# Ethernet.net
KiCad netlist of a schematic drawn in Altium Designer
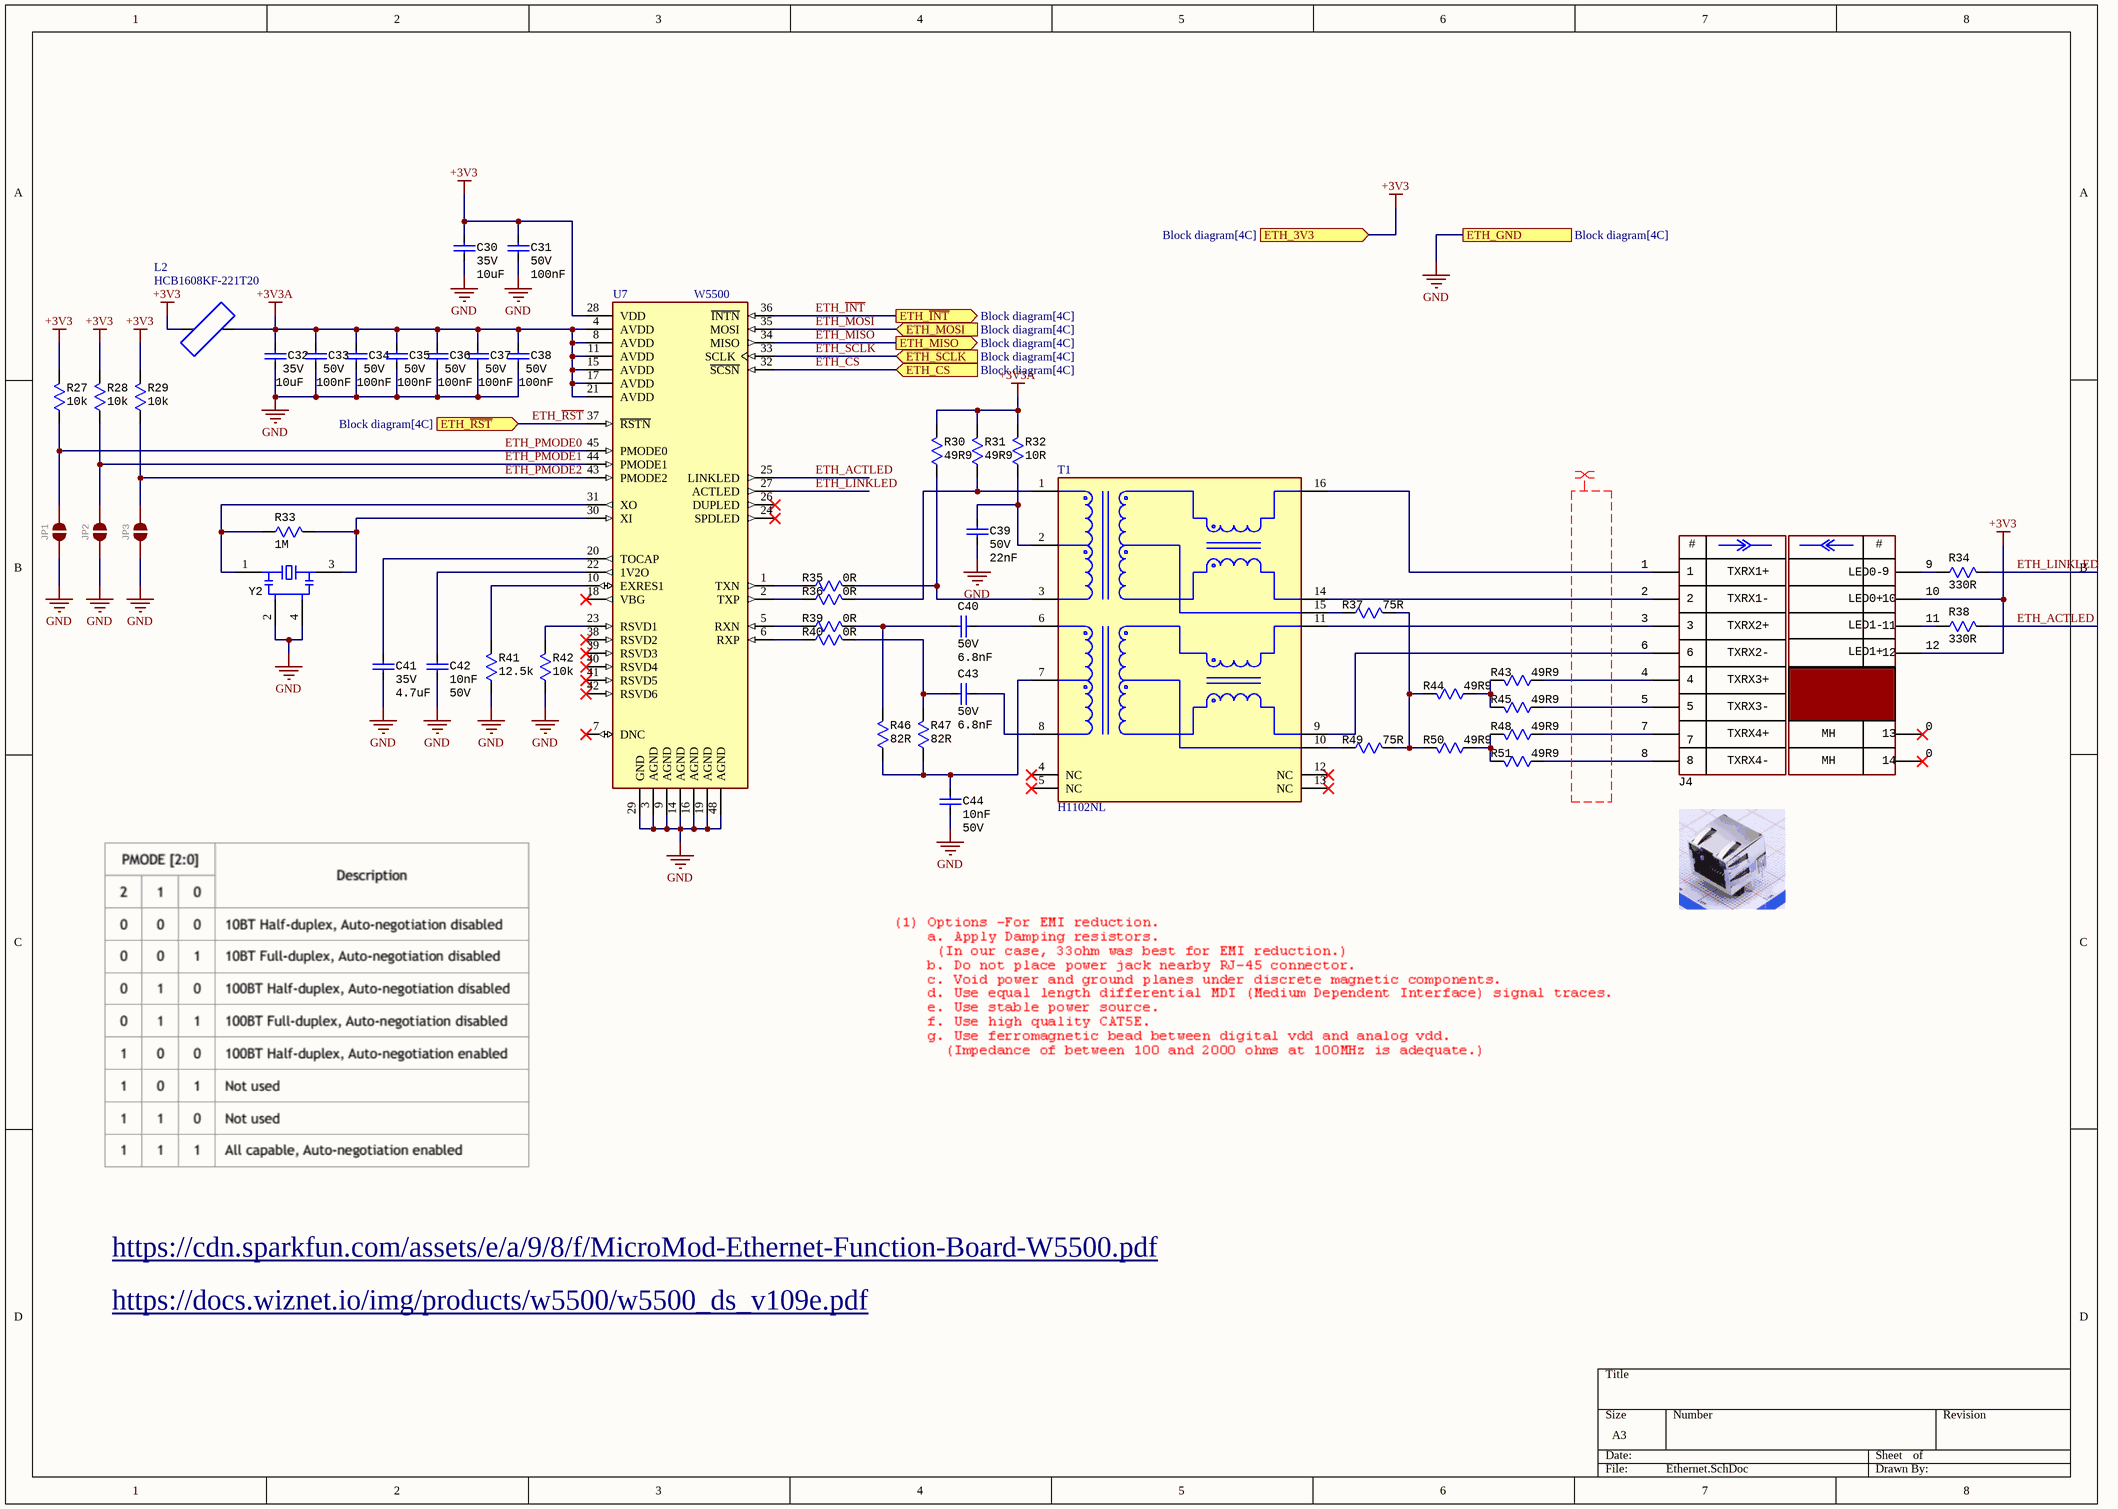
[diagram p0: Ethernet.SchDoc]

(export (version "E")
  (design (tool "Eeschema 10.0.6"))
  (components
    (comp (ref "C30")
      (value "10uF")
      (footprint "CAP Ceramic SMD 0603")
      (description "Cap Ceramic 10uF 35V X5R 20% Pad SMD 0603 85C T/R")
      (fields
        (field (name "MANUFACTURER") "Murata")
        (field (name "MANUFACTURER PART NUMBER") "GRM188R6YA106MA73D")
        (field (name "VOLTAGE") "35V")
      )
      (libsource (lib "Passive") (part "CAP 0603 10uF 35V"))
    )
    (comp (ref "C31")
      (value "100nF")
      (footprint "CAP Ceramic SMD 0603")
      (description "Multilayer Ceramic Capacitors MLCC Surface Mount 0603 0.1uF 50 Volts X7R 10%")
      (fields
        (field (name "MANUFACTURER") "Murata")
        (field (name "MANUFACTURER PART NUMBER") "GRM188R71H104KA93D")
        (field (name "VOLTAGE") "50V")
      )
      (libsource (lib "Passive") (part "CAP 0603 100nF 50V"))
    )
    (comp (ref "C32")
      (value "10uF")
      (footprint "CAP Ceramic SMD 0603")
      (description "Cap Ceramic 10uF 35V X5R 20% Pad SMD 0603 85C T/R")
      (fields
        (field (name "MANUFACTURER") "Murata")
        (field (name "MANUFACTURER PART NUMBER") "GRM188R6YA106MA73D")
        (field (name "VOLTAGE") "35V")
      )
      (libsource (lib "Passive") (part "CAP 0603 10uF 35V"))
    )
    (comp (ref "C33")
      (value "100nF")
      (footprint "CAP Ceramic SMD 0603")
      (description "Multilayer Ceramic Capacitors MLCC Surface Mount 0603 0.1uF 50 Volts X7R 10%")
      (fields
        (field (name "MANUFACTURER") "Murata")
        (field (name "MANUFACTURER PART NUMBER") "GRM188R71H104KA93D")
        (field (name "VOLTAGE") "50V")
      )
      (libsource (lib "Passive") (part "CAP 0603 100nF 50V"))
    )
    (comp (ref "C34")
      (value "100nF")
      (footprint "CAP Ceramic SMD 0603")
      (description "Multilayer Ceramic Capacitors MLCC Surface Mount 0603 0.1uF 50 Volts X7R 10%")
      (fields
        (field (name "MANUFACTURER") "Murata")
        (field (name "MANUFACTURER PART NUMBER") "GRM188R71H104KA93D")
        (field (name "VOLTAGE") "50V")
      )
      (libsource (lib "Passive") (part "CAP 0603 100nF 50V"))
    )
    (comp (ref "C35")
      (value "100nF")
      (footprint "CAP Ceramic SMD 0603")
      (description "Multilayer Ceramic Capacitors MLCC Surface Mount 0603 0.1uF 50 Volts X7R 10%")
      (fields
        (field (name "MANUFACTURER") "Murata")
        (field (name "MANUFACTURER PART NUMBER") "GRM188R71H104KA93D")
        (field (name "VOLTAGE") "50V")
      )
      (libsource (lib "Passive") (part "CAP 0603 100nF 50V"))
    )
    (comp (ref "C36")
      (value "100nF")
      (footprint "CAP Ceramic SMD 0603")
      (description "Multilayer Ceramic Capacitors MLCC Surface Mount 0603 0.1uF 50 Volts X7R 10%")
      (fields
        (field (name "MANUFACTURER") "Murata")
        (field (name "MANUFACTURER PART NUMBER") "GRM188R71H104KA93D")
        (field (name "VOLTAGE") "50V")
      )
      (libsource (lib "Passive") (part "CAP 0603 100nF 50V"))
    )
    (comp (ref "C37")
      (value "100nF")
      (footprint "CAP Ceramic SMD 0603")
      (description "Multilayer Ceramic Capacitors MLCC Surface Mount 0603 0.1uF 50 Volts X7R 10%")
      (fields
        (field (name "MANUFACTURER") "Murata")
        (field (name "MANUFACTURER PART NUMBER") "GRM188R71H104KA93D")
        (field (name "VOLTAGE") "50V")
      )
      (libsource (lib "Passive") (part "CAP 0603 100nF 50V"))
    )
    (comp (ref "C38")
      (value "100nF")
      (footprint "CAP Ceramic SMD 0603")
      (description "Multilayer Ceramic Capacitors MLCC Surface Mount 0603 0.1uF 50 Volts X7R 10%")
      (fields
        (field (name "MANUFACTURER") "Murata")
        (field (name "MANUFACTURER PART NUMBER") "GRM188R71H104KA93D")
        (field (name "VOLTAGE") "50V")
      )
      (libsource (lib "Passive") (part "CAP 0603 100nF 50V"))
    )
    (comp (ref "C39")
      (value "22nF")
      (footprint "CAP Ceramic SMD 0603")
      (description "Ceramic capacitor SMD-0603 22nF /50V X7R# K +-10%, Samsung, RoHS")
      (fields
        (field (name "MANUFACTURER") "Samsung")
        (field (name "MANUFACTURER PART NUMBER") "CL10B223KB8NNNC")
        (field (name "VOLTAGE") "50V")
        (field (name "CAPACITANCE") "22nF")
      )
      (libsource (lib "Passive") (part "CAP 0603 22nF 50V"))
    )
    (comp (ref "C40")
      (value "6.8nF")
      (footprint "CAP Ceramic SMD 0603")
      (description "Cap Ceramic 0.0068uF 50V X7R 5% SMD 0603 125°C Paper T/R")
      (fields
        (field (name "MANUFACTURER") "Yageo")
        (field (name "PART NUMBER") "CC0201KRX7R7BB103")
        (field (name "VOLTAGE") "50V")
        (field (name "CAPACITANCE") "6.8nF")
      )
      (libsource (lib "Passive") (part "CAP 0603 6.8nF 50V"))
    )
    (comp (ref "C41")
      (value "4.7uF")
      (footprint "CAP Ceramic SMD 0603")
      (description "Multilayer Ceramic Capacitor, 4.7 uF, 35 V, ± 10%, X5R, 0603 [1608 Metric]")
      (fields
        (field (name "MANUFACTURER") "Murata")
        (field (name "MANUFACTURER PART NUMBER") "GRM188R6YA475KE15D")
        (field (name "VOLTAGE") "35V")
      )
      (libsource (lib "Passive") (part "CAP 0603 4.7uF 35V"))
    )
    (comp (ref "C42")
      (value "10nF")
      (footprint "CAP Ceramic SMD 0603")
      (description "0603 10nF 50V ±10% Tolerance X7R Surface Mount Multilayer Ceramic Capacitor")
      (fields
        (field (name "MANUFACTURER") "Kyocera AVX")
        (field (name "MANUFACTURER PART NUMBER") "06035C103K4T2A")
        (field (name "CAPACITANCE") "10nF")
        (field (name "VOLTAGE RATING") "50V")
      )
      (libsource (lib "Passive") (part "CAP 0603 10nF 50V"))
    )
    (comp (ref "C43")
      (value "6.8nF")
      (footprint "CAP Ceramic SMD 0603")
      (description "Cap Ceramic 0.0068uF 50V X7R 5% SMD 0603 125°C Paper T/R")
      (fields
        (field (name "MANUFACTURER") "Yageo")
        (field (name "PART NUMBER") "CC0201KRX7R7BB103")
        (field (name "VOLTAGE") "50V")
        (field (name "CAPACITANCE") "6.8nF")
      )
      (libsource (lib "Passive") (part "CAP 0603 6.8nF 50V"))
    )
    (comp (ref "C44")
      (value "10nF")
      (footprint "CAP Ceramic SMD 0603")
      (description "0603 10nF 50V ±10% Tolerance X7R Surface Mount Multilayer Ceramic Capacitor")
      (fields
        (field (name "MANUFACTURER") "Kyocera AVX")
        (field (name "MANUFACTURER PART NUMBER") "06035C103K4T2A")
        (field (name "CAPACITANCE") "10nF")
        (field (name "VOLTAGE RATING") "50V")
      )
      (libsource (lib "Passive") (part "CAP 0603 10nF 50V"))
    )
    (comp (ref "J4")
      (value "RJ45-B-1*1")
      (footprint "Connector RJ-45 (615008137421 / DS1128-09-S8B8S)")
      (description "RJ45 RJReceptacle 1 Plugin Ethernet Connectors/Modular Connectors (RJ45 RJ11) ROHS")
      (fields (field (name "MANUFACTURER") "BOOMELE(Boom Precision Elec)"))
      (libsource (lib "Signal connectors") (part "RJ45-B-1*1"))
    )
    (comp (ref "JP1")
      (value "JUMPER-SMT_2_NO_SILK_ROUND")
      (footprint "SMT-JUMPER_2_NO_SILK_ROUND")
      (libsource (lib "Bypass, Testpoint and Holes") (part "JUMPER-SMT_2_NO_SILK_ROUND"))
    )
    (comp (ref "JP2")
      (value "JUMPER-SMT_2_NO_SILK_ROUND")
      (footprint "SMT-JUMPER_2_NO_SILK_ROUND")
      (libsource (lib "Bypass, Testpoint and Holes") (part "JUMPER-SMT_2_NO_SILK_ROUND"))
    )
    (comp (ref "JP3")
      (value "JUMPER-SMT_2_NO_SILK_ROUND")
      (footprint "SMT-JUMPER_2_NO_SILK_ROUND")
      (libsource (lib "Bypass, Testpoint and Holes") (part "JUMPER-SMT_2_NO_SILK_ROUND"))
    )
    (comp (ref "L2")
      (value "HCB1608KF-221T20")
      (footprint "HCB1608KF-221T20")
      (description "2A 1 100mΩ 220Ω@100MHz ±25% 0603 Ferrite Beads ROHS")
      (fields (field (name "MANUFACTURER") "TAI-TECH"))
      (libsource (lib "Passive") (part "Ferrite-Bead"))
    )
    (comp (ref "R27")
      (value "10k")
      (footprint "RES SMD 0603")
      (description "Res Thick Film 0603 10K Ohm 1% 1/10W ±100ppm/°C Molded SMD Punched Carrier T/R")
      (fields
        (field (name "MANUFACTURER") "Panasonic")
        (field (name "MANUFACTURER PART NUMBER") "ERJ-3EKF1002V")
      )
      (libsource (lib "Passive") (part "RES 0603 10k 1%"))
    )
    (comp (ref "R28")
      (value "10k")
      (footprint "RES SMD 0603")
      (description "Res Thick Film 0603 10K Ohm 1% 1/10W ±100ppm/°C Molded SMD Punched Carrier T/R")
      (fields
        (field (name "MANUFACTURER") "Panasonic")
        (field (name "MANUFACTURER PART NUMBER") "ERJ-3EKF1002V")
      )
      (libsource (lib "Passive") (part "RES 0603 10k 1%"))
    )
    (comp (ref "R29")
      (value "10k")
      (footprint "RES SMD 0603")
      (description "Res Thick Film 0603 10K Ohm 1% 1/10W ±100ppm/°C Molded SMD Punched Carrier T/R")
      (fields
        (field (name "MANUFACTURER") "Panasonic")
        (field (name "MANUFACTURER PART NUMBER") "ERJ-3EKF1002V")
      )
      (libsource (lib "Passive") (part "RES 0603 10k 1%"))
    )
    (comp (ref "R30")
      (value "49R9")
      (footprint "RES SMD 0603")
      (description "Res General Purpose Thick Film 0603 49.9 Ohm 1% 1/10W ±100ppm/°C Molded SMD Paper T/R")
      (fields
        (field (name "MANUFACTURER") "Yageo")
        (field (name "MANUFACTURER PART NUMBER") "RC0603FR-0749R9L")
      )
      (libsource (lib "Passive") (part "RES 0603 49R9 1%"))
    )
    (comp (ref "R31")
      (value "49R9")
      (footprint "RES SMD 0603")
      (description "Res General Purpose Thick Film 0603 49.9 Ohm 1% 1/10W ±100ppm/°C Molded SMD Paper T/R")
      (fields
        (field (name "MANUFACTURER") "Yageo")
        (field (name "MANUFACTURER PART NUMBER") "RC0603FR-0749R9L")
      )
      (libsource (lib "Passive") (part "RES 0603 49R9 1%"))
    )
    (comp (ref "R32")
      (value "10R")
      (footprint "RES SMD 0603")
      (description "Res Thick Film 0603 10 Ohm 1% 1/10W ±200ppm/°C Molded SMD Paper T/R")
      (fields
        (field (name "MANUFACTURER") "Yageo")
        (field (name "MANUFACTURER PART NUMBER") "RC0603FR-0710RL")
      )
      (libsource (lib "Passive") (part "RES 0603 10R 1%"))
    )
    (comp (ref "R33")
      (value "1M")
      (footprint "RES SMD 0603")
      (description "Res Thick Film 0603 1M Ohm 1% 1/10W ±100ppm/°C Molded SMD Punched Carrier T/R")
      (fields
        (field (name "MANUFACTURER") "Vishay")
        (field (name "MANUFACTURER PART NUMBER") "CRCW06031M00FKEA")
      )
      (libsource (lib "Passive") (part "RES 0603 1M 1%"))
    )
    (comp (ref "R34")
      (value "330R")
      (footprint "RES SMD 0603")
      (description "YAGEO (PHYCOMP) - RC0603FR-07330RL - RES, THICK FILM, 330R, 1%, 0.1W, 0603")
      (fields
        (field (name "MANUFACTURER") "Yageo")
        (field (name "MANUFACTURER PART NUMBER") "RC0603FR-07330RL")
        (field (name "RESISTANCE") "330R")
      )
      (libsource (lib "Passive") (part "RES 0603 330R 1%"))
    )
    (comp (ref "R35")
      (value "0R")
      (footprint "RES SMD 0603")
      (description "ERJ Series 0603 0 Ohm 0.05 W Jumper Surface Mount Thick Film Chip Resistor")
      (fields (field (name "TOLERANCE") "1%") (field (name "MANUFACTURER") "Panasonic"))
      (libsource (lib "Passive") (part "RES 0603 0R 1%"))
    )
    (comp (ref "R36")
      (value "0R")
      (footprint "RES SMD 0603")
      (description "ERJ Series 0603 0 Ohm 0.05 W Jumper Surface Mount Thick Film Chip Resistor")
      (fields (field (name "TOLERANCE") "1%") (field (name "MANUFACTURER") "Panasonic"))
      (libsource (lib "Passive") (part "RES 0603 0R 1%"))
    )
    (comp (ref "R37")
      (value "75R")
      (footprint "RES SMD 0603")
      (description "Resistor Thick Film 0603 75 Ohm 1% 1/10W 100ppm/C Molded SMD Punched Carrier T/R")
      (fields
        (field (name "MANUFACTURER") "Panasonic")
        (field (name "MANUFACTURER PART NUMBER") "ERJ-3EKF75R0V")
      )
      (libsource (lib "Passive") (part "RES 0603 75R 1%"))
    )
    (comp (ref "R38")
      (value "330R")
      (footprint "RES SMD 0603")
      (description "YAGEO (PHYCOMP) - RC0603FR-07330RL - RES, THICK FILM, 330R, 1%, 0.1W, 0603")
      (fields
        (field (name "MANUFACTURER") "Yageo")
        (field (name "MANUFACTURER PART NUMBER") "RC0603FR-07330RL")
        (field (name "RESISTANCE") "330R")
      )
      (libsource (lib "Passive") (part "RES 0603 330R 1%"))
    )
    (comp (ref "R39")
      (value "0R")
      (footprint "RES SMD 0603")
      (description "ERJ Series 0603 0 Ohm 0.05 W Jumper Surface Mount Thick Film Chip Resistor")
      (fields (field (name "TOLERANCE") "1%") (field (name "MANUFACTURER") "Panasonic"))
      (libsource (lib "Passive") (part "RES 0603 0R 1%"))
    )
    (comp (ref "R40")
      (value "0R")
      (footprint "RES SMD 0603")
      (description "ERJ Series 0603 0 Ohm 0.05 W Jumper Surface Mount Thick Film Chip Resistor")
      (fields (field (name "TOLERANCE") "1%") (field (name "MANUFACTURER") "Panasonic"))
      (libsource (lib "Passive") (part "RES 0603 0R 1%"))
    )
    (comp (ref "R41")
      (value "12.5k")
      (footprint "RES SMD 0603")
      (description "Res Thick Film 0603 12.4K Ohm 1% 1/10W ±100ppm/°C Molded SMD SMD Paper Tape on Plastic Reel")
      (fields
        (field (name "MANUFACTURER") "Bourns")
        (field (name "MANUFACTURER PART NUMBER") "CR0603-FX-1242ELF")
      )
      (libsource (lib "Passive") (part "RES 0603 12.5k 1%"))
    )
    (comp (ref "R42")
      (value "10k")
      (footprint "RES SMD 0603")
      (description "Res Thick Film 0603 10K Ohm 1% 1/10W ±100ppm/°C Molded SMD Punched Carrier T/R")
      (fields
        (field (name "MANUFACTURER") "Panasonic")
        (field (name "MANUFACTURER PART NUMBER") "ERJ-3EKF1002V")
      )
      (libsource (lib "Passive") (part "RES 0603 10k 1%"))
    )
    (comp (ref "R43")
      (value "49R9")
      (footprint "RES SMD 0603")
      (description "Res General Purpose Thick Film 0603 49.9 Ohm 1% 1/10W ±100ppm/°C Molded SMD Paper T/R")
      (fields
        (field (name "MANUFACTURER") "Yageo")
        (field (name "MANUFACTURER PART NUMBER") "RC0603FR-0749R9L")
      )
      (libsource (lib "Passive") (part "RES 0603 49R9 1%"))
    )
    (comp (ref "R44")
      (value "49R9")
      (footprint "RES SMD 0603")
      (description "Res General Purpose Thick Film 0603 49.9 Ohm 1% 1/10W ±100ppm/°C Molded SMD Paper T/R")
      (fields
        (field (name "MANUFACTURER") "Yageo")
        (field (name "MANUFACTURER PART NUMBER") "RC0603FR-0749R9L")
      )
      (libsource (lib "Passive") (part "RES 0603 49R9 1%"))
    )
    (comp (ref "R45")
      (value "49R9")
      (footprint "RES SMD 0603")
      (description "Res General Purpose Thick Film 0603 49.9 Ohm 1% 1/10W ±100ppm/°C Molded SMD Paper T/R")
      (fields
        (field (name "MANUFACTURER") "Yageo")
        (field (name "MANUFACTURER PART NUMBER") "RC0603FR-0749R9L")
      )
      (libsource (lib "Passive") (part "RES 0603 49R9 1%"))
    )
    (comp (ref "R46")
      (value "82R")
      (footprint "RES SMD 0603")
      (description "Res Thick Film 0603 82 Ohm 1% 0.1W(1/10W) ±100ppm/C Pad SMD T/R")
      (fields
        (field (name "MANUFACTURER") "Yageo")
        (field (name "MANUFACTURER PART NUMBER") "RC0603FR-0782RL")
        (field (name "RESISTANCE") "82R")
      )
      (libsource (lib "Passive") (part "RES 0603 82R 1%"))
    )
    (comp (ref "R47")
      (value "82R")
      (footprint "RES SMD 0603")
      (description "Res Thick Film 0603 82 Ohm 1% 0.1W(1/10W) ±100ppm/C Pad SMD T/R")
      (fields
        (field (name "MANUFACTURER") "Yageo")
        (field (name "MANUFACTURER PART NUMBER") "RC0603FR-0782RL")
        (field (name "RESISTANCE") "82R")
      )
      (libsource (lib "Passive") (part "RES 0603 82R 1%"))
    )
    (comp (ref "R48")
      (value "49R9")
      (footprint "RES SMD 0603")
      (description "Res General Purpose Thick Film 0603 49.9 Ohm 1% 1/10W ±100ppm/°C Molded SMD Paper T/R")
      (fields
        (field (name "MANUFACTURER") "Yageo")
        (field (name "MANUFACTURER PART NUMBER") "RC0603FR-0749R9L")
      )
      (libsource (lib "Passive") (part "RES 0603 49R9 1%"))
    )
    (comp (ref "R49")
      (value "75R")
      (footprint "RES SMD 0603")
      (description "Resistor Thick Film 0603 75 Ohm 1% 1/10W 100ppm/C Molded SMD Punched Carrier T/R")
      (fields
        (field (name "MANUFACTURER") "Panasonic")
        (field (name "MANUFACTURER PART NUMBER") "ERJ-3EKF75R0V")
      )
      (libsource (lib "Passive") (part "RES 0603 75R 1%"))
    )
    (comp (ref "R50")
      (value "49R9")
      (footprint "RES SMD 0603")
      (description "Res General Purpose Thick Film 0603 49.9 Ohm 1% 1/10W ±100ppm/°C Molded SMD Paper T/R")
      (fields
        (field (name "MANUFACTURER") "Yageo")
        (field (name "MANUFACTURER PART NUMBER") "RC0603FR-0749R9L")
      )
      (libsource (lib "Passive") (part "RES 0603 49R9 1%"))
    )
    (comp (ref "R51")
      (value "49R9")
      (footprint "RES SMD 0603")
      (description "Res General Purpose Thick Film 0603 49.9 Ohm 1% 1/10W ±100ppm/°C Molded SMD Paper T/R")
      (fields
        (field (name "MANUFACTURER") "Yageo")
        (field (name "MANUFACTURER PART NUMBER") "RC0603FR-0749R9L")
      )
      (libsource (lib "Passive") (part "RES 0603 49R9 1%"))
    )
    (comp (ref "T1")
      (value "H1102NL")
      (footprint "FP-H1102NL-MFG")
      (description "Telecom RJ45 Transformer 1:1/1:1 16Term. Gull Wing SMD")
      (fields (field (name "MANUFACTURER") "Pulse"))
      (libsource (lib "Passive") (part "H1102NLT"))
    )
    (comp (ref "U7")
      (value "W5500")
      (footprint "QFP50P900X900X160-48N")
      (description "IC CTLR 3-1 ETH TCP/IP 48LQFP")
      (fields (field (name "MANUFACTURER") "WIZnet"))
      (libsource (lib "Communictation ICs") (part "W5500"))
    )
    (comp (ref "Y2")
      (value "X322525MRB4SI")
      (footprint "Crystal SMD 4-PIN 3225")
      (description "25MHz SMD Crystal Resonator 18pF ±10ppm ±30ppm -40℃~+85℃ SMD3225-4P Crystals ROHS")
      (fields (field (name "MANUFACTURER") "YXC"))
      (libsource (lib "Crystal") (part "X322525MRB4SI"))
    )
  )
  (nets
    (net (code "1") (name "+3V3") (class "Default")
      (node (ref "C30") (pin "1") (pinfunction "1_1") (pintype "passive"))
      (node (ref "C31") (pin "1") (pinfunction "1_1") (pintype "passive"))
      (node (ref "J4") (pin "10") (pinfunction "10_10") (pintype "passive"))
      (node (ref "J4") (pin "12") (pinfunction "12_12") (pintype "passive"))
      (node (ref "L2") (pin "2") (pinfunction "2_2") (pintype "passive"))
      (node (ref "R27") (pin "2") (pinfunction "2_2") (pintype "passive"))
      (node (ref "R28") (pin "2") (pinfunction "2_2") (pintype "passive"))
      (node (ref "R29") (pin "2") (pinfunction "2_2") (pintype "passive"))
      (node (ref "U7") (pin "28") (pinfunction "VDD_28") (pintype "power_in"))
    )
    (net (code "2") (name "+3V3A") (class "Default")
      (node (ref "C32") (pin "1") (pinfunction "1_1") (pintype "passive"))
      (node (ref "C33") (pin "1") (pinfunction "1_1") (pintype "passive"))
      (node (ref "C34") (pin "1") (pinfunction "1_1") (pintype "passive"))
      (node (ref "C35") (pin "1") (pinfunction "1_1") (pintype "passive"))
      (node (ref "C36") (pin "1") (pinfunction "1_1") (pintype "passive"))
      (node (ref "C37") (pin "1") (pinfunction "1_1") (pintype "passive"))
      (node (ref "C38") (pin "1") (pinfunction "1_1") (pintype "passive"))
      (node (ref "L2") (pin "1") (pinfunction "1_1") (pintype "passive"))
      (node (ref "R30") (pin "2") (pinfunction "2_2") (pintype "passive"))
      (node (ref "R31") (pin "2") (pinfunction "2_2") (pintype "passive"))
      (node (ref "R32") (pin "2") (pinfunction "2_2") (pintype "passive"))
      (node (ref "U7") (pin "11") (pinfunction "AVDD_11") (pintype "power_in"))
      (node (ref "U7") (pin "15") (pinfunction "AVDD_15") (pintype "power_in"))
      (node (ref "U7") (pin "17") (pinfunction "AVDD_17") (pintype "power_in"))
      (node (ref "U7") (pin "21") (pinfunction "AVDD_21") (pintype "power_in"))
      (node (ref "U7") (pin "4") (pinfunction "AVDD_4") (pintype "power_in"))
      (node (ref "U7") (pin "8") (pinfunction "AVDD_8") (pintype "power_in"))
    )
    (net (code "3") (name "/ETH_ACTLED") (class "Default")
      (node (ref "R38") (pin "2") (pinfunction "2_2") (pintype "passive"))
      (node (ref "U7") (pin "25") (pinfunction "LINKLED_25") (pintype "output"))
    )
    (net (code "4") (name "/ETH_CS") (class "Default")
      (node (ref "U7") (pin "32") (pinfunction "~{SCSN}_32") (pintype "input"))
    )
    (net (code "5") (name "/ETH_LINKLED") (class "Default")
      (node (ref "R34") (pin "2") (pinfunction "2_2") (pintype "passive"))
      (node (ref "U7") (pin "27") (pinfunction "ACTLED_27") (pintype "output"))
    )
    (net (code "6") (name "/ETH_MISO") (class "Default")
      (node (ref "U7") (pin "34") (pinfunction "MISO_34") (pintype "output"))
    )
    (net (code "7") (name "/ETH_MOSI") (class "Default")
      (node (ref "U7") (pin "35") (pinfunction "MOSI_35") (pintype "input"))
    )
    (net (code "8") (name "/ETH_PMODE0") (class "Default")
      (node (ref "JP1") (pin "2") (pinfunction "2_2") (pintype "passive"))
      (node (ref "R27") (pin "1") (pinfunction "1_1") (pintype "passive"))
      (node (ref "U7") (pin "45") (pinfunction "PMODE0_45") (pintype "input"))
    )
    (net (code "9") (name "/ETH_PMODE1") (class "Default")
      (node (ref "JP2") (pin "2") (pinfunction "2_2") (pintype "passive"))
      (node (ref "R28") (pin "1") (pinfunction "1_1") (pintype "passive"))
      (node (ref "U7") (pin "44") (pinfunction "PMODE1_44") (pintype "input"))
    )
    (net (code "10") (name "/ETH_PMODE2") (class "Default")
      (node (ref "JP3") (pin "2") (pinfunction "2_2") (pintype "passive"))
      (node (ref "R29") (pin "1") (pinfunction "1_1") (pintype "passive"))
      (node (ref "U7") (pin "43") (pinfunction "PMODE2_43") (pintype "input"))
    )
    (net (code "11") (name "/ETH_SCLK") (class "Default")
      (node (ref "U7") (pin "33") (pinfunction "SCLK_33") (pintype "input"))
    )
    (net (code "12") (name "/ETH_~{INT}") (class "Default")
      (node (ref "U7") (pin "36") (pinfunction "~{INTN}_36") (pintype "input"))
    )
    (net (code "13") (name "/ETH_~{RST}") (class "Default")
      (node (ref "U7") (pin "37") (pinfunction "~{RSTN}_37") (pintype "input"))
    )
    (net (code "14") (name "GND") (class "Default")
      (node (ref "C30") (pin "2") (pinfunction "2_2") (pintype "passive"))
      (node (ref "C31") (pin "2") (pinfunction "2_2") (pintype "passive"))
      (node (ref "C32") (pin "2") (pinfunction "2_2") (pintype "passive"))
      (node (ref "C33") (pin "2") (pinfunction "2_2") (pintype "passive"))
      (node (ref "C34") (pin "2") (pinfunction "2_2") (pintype "passive"))
      (node (ref "C35") (pin "2") (pinfunction "2_2") (pintype "passive"))
      (node (ref "C36") (pin "2") (pinfunction "2_2") (pintype "passive"))
      (node (ref "C37") (pin "2") (pinfunction "2_2") (pintype "passive"))
      (node (ref "C38") (pin "2") (pinfunction "2_2") (pintype "passive"))
      (node (ref "C39") (pin "2") (pinfunction "2_2") (pintype "passive"))
      (node (ref "C41") (pin "2") (pinfunction "2_2") (pintype "passive"))
      (node (ref "C42") (pin "2") (pinfunction "2_2") (pintype "passive"))
      (node (ref "C44") (pin "2") (pinfunction "2_2") (pintype "passive"))
      (node (ref "JP1") (pin "1") (pinfunction "1_1") (pintype "passive"))
      (node (ref "JP2") (pin "1") (pinfunction "1_1") (pintype "passive"))
      (node (ref "JP3") (pin "1") (pinfunction "1_1") (pintype "passive"))
      (node (ref "R41") (pin "1") (pinfunction "1_1") (pintype "passive"))
      (node (ref "R42") (pin "1") (pinfunction "1_1") (pintype "passive"))
      (node (ref "U7") (pin "14") (pinfunction "AGND_14") (pintype "power_in"))
      (node (ref "U7") (pin "16") (pinfunction "AGND_16") (pintype "power_in"))
      (node (ref "U7") (pin "19") (pinfunction "AGND_19") (pintype "power_in"))
      (node (ref "U7") (pin "29") (pinfunction "GND_29") (pintype "passive"))
      (node (ref "U7") (pin "3") (pinfunction "AGND_3") (pintype "power_in"))
      (node (ref "U7") (pin "48") (pinfunction "AGND_48") (pintype "power_in"))
      (node (ref "U7") (pin "9") (pinfunction "AGND_9") (pintype "power_in"))
      (node (ref "Y2") (pin "2") (pinfunction "NC_2") (pintype "passive"))
      (node (ref "Y2") (pin "4") (pinfunction "4_4") (pintype "passive"))
    )
    (net (code "15") (name "Net-(C39-Pad1)") (class "Default")
      (node (ref "C39") (pin "1") (pinfunction "1_1") (pintype "passive"))
      (node (ref "R32") (pin "1") (pinfunction "1_1") (pintype "passive"))
      (node (ref "T1") (pin "2") (pinfunction "CT_2") (pintype "passive"))
    )
    (net (code "16") (name "Net-(C40-Pad1)") (class "Default")
      (node (ref "C40") (pin "1") (pinfunction "1_1") (pintype "passive"))
      (node (ref "R39") (pin "2") (pinfunction "2_2") (pintype "passive"))
      (node (ref "R46") (pin "2") (pinfunction "2_2") (pintype "passive"))
    )
    (net (code "17") (name "Net-(C43-Pad1)") (class "Default")
      (node (ref "C43") (pin "1") (pinfunction "1_1") (pintype "passive"))
      (node (ref "R40") (pin "2") (pinfunction "2_2") (pintype "passive"))
      (node (ref "R47") (pin "2") (pinfunction "2_2") (pintype "passive"))
    )
    (net (code "18") (name "Net-(C44-Pad1)") (class "Default")
      (node (ref "C44") (pin "1") (pinfunction "1_1") (pintype "passive"))
      (node (ref "R46") (pin "1") (pinfunction "1_1") (pintype "passive"))
      (node (ref "R47") (pin "1") (pinfunction "1_1") (pintype "passive"))
      (node (ref "T1") (pin "7") (pinfunction "CT_7") (pintype "passive"))
    )
    (net (code "19") (name "Net-(J4-Pad4)") (class "Default")
      (node (ref "J4") (pin "4") (pinfunction "4_4") (pintype "passive"))
      (node (ref "R43") (pin "1") (pinfunction "1_1") (pintype "passive"))
    )
    (net (code "20") (name "Net-(J4-Pad5)") (class "Default")
      (node (ref "J4") (pin "5") (pinfunction "5_5") (pintype "passive"))
      (node (ref "R45") (pin "1") (pinfunction "1_1") (pintype "passive"))
    )
    (net (code "21") (name "Net-(J4-Pad7)") (class "Default")
      (node (ref "J4") (pin "7") (pinfunction "7_7") (pintype "passive"))
      (node (ref "R48") (pin "1") (pinfunction "1_1") (pintype "passive"))
    )
    (net (code "22") (name "Net-(J4-Pad8)") (class "Default")
      (node (ref "J4") (pin "8") (pinfunction "8_8") (pintype "passive"))
      (node (ref "R51") (pin "1") (pinfunction "1_1") (pintype "passive"))
    )
    (net (code "23") (name "Net-(J4-Pad9)") (class "Default")
      (node (ref "J4") (pin "9") (pinfunction "9_9") (pintype "passive"))
      (node (ref "R34") (pin "1") (pinfunction "1_1") (pintype "passive"))
    )
    (net (code "24") (name "Net-(J4-Pad11)") (class "Default")
      (node (ref "J4") (pin "11") (pinfunction "11_11") (pintype "passive"))
      (node (ref "R38") (pin "1") (pinfunction "1_1") (pintype "passive"))
    )
    (net (code "25") (name "Net-(R37-Pad1)") (class "Default")
      (node (ref "R37") (pin "1") (pinfunction "1_1") (pintype "passive"))
      (node (ref "T1") (pin "15") (pinfunction "NC_15") (pintype "passive"))
    )
    (net (code "26") (name "Net-(R37-Pad2)") (class "Default")
      (node (ref "R37") (pin "2") (pinfunction "2_2") (pintype "passive"))
      (node (ref "R44") (pin "2") (pinfunction "2_2") (pintype "passive"))
      (node (ref "R49") (pin "2") (pinfunction "2_2") (pintype "passive"))
      (node (ref "R50") (pin "2") (pinfunction "2_2") (pintype "passive"))
    )
    (net (code "27") (name "Net-(R43-Pad2)") (class "Default")
      (node (ref "R43") (pin "2") (pinfunction "2_2") (pintype "passive"))
      (node (ref "R44") (pin "1") (pinfunction "1_1") (pintype "passive"))
      (node (ref "R45") (pin "2") (pinfunction "2_2") (pintype "passive"))
    )
    (net (code "28") (name "Net-(R48-Pad2)") (class "Default")
      (node (ref "R48") (pin "2") (pinfunction "2_2") (pintype "passive"))
      (node (ref "R50") (pin "1") (pinfunction "1_1") (pintype "passive"))
      (node (ref "R51") (pin "2") (pinfunction "2_2") (pintype "passive"))
    )
    (net (code "29") (name "Net-(R49-Pad1)") (class "Default")
      (node (ref "R49") (pin "1") (pinfunction "1_1") (pintype "passive"))
      (node (ref "T1") (pin "10") (pinfunction "NC_10") (pintype "passive"))
    )
    (net (code "30") (name "Net-(T1-RD+)") (class "Default")
      (node (ref "C40") (pin "2") (pinfunction "2_2") (pintype "passive"))
      (node (ref "T1") (pin "6") (pinfunction "RD+_6") (pintype "passive"))
    )
    (net (code "31") (name "Net-(T1-RD-)") (class "Default")
      (node (ref "C43") (pin "2") (pinfunction "2_2") (pintype "passive"))
      (node (ref "T1") (pin "8") (pinfunction "RD-_8") (pintype "passive"))
    )
    (net (code "32") (name "Net-(T1-RX+)") (class "Default")
      (node (ref "J4") (pin "3") (pinfunction "3_3") (pintype "passive"))
      (node (ref "T1") (pin "11") (pinfunction "RX+_11") (pintype "passive"))
    )
    (net (code "33") (name "Net-(T1-RX-)") (class "Default")
      (node (ref "J4") (pin "6") (pinfunction "6_6") (pintype "passive"))
      (node (ref "T1") (pin "9") (pinfunction "RX-_9") (pintype "passive"))
    )
    (net (code "34") (name "Net-(T1-TD+)") (class "Default")
      (node (ref "R31") (pin "1") (pinfunction "1_1") (pintype "passive"))
      (node (ref "R36") (pin "2") (pinfunction "2_2") (pintype "passive"))
      (node (ref "T1") (pin "1") (pinfunction "TD+_1") (pintype "passive"))
    )
    (net (code "35") (name "Net-(T1-TD-)") (class "Default")
      (node (ref "R30") (pin "1") (pinfunction "1_1") (pintype "passive"))
      (node (ref "R35") (pin "2") (pinfunction "2_2") (pintype "passive"))
      (node (ref "T1") (pin "3") (pinfunction "TD-_3") (pintype "passive"))
    )
    (net (code "36") (name "Net-(T1-TX+)") (class "Default")
      (node (ref "J4") (pin "1") (pinfunction "1_1") (pintype "passive"))
      (node (ref "T1") (pin "16") (pinfunction "TX+_16") (pintype "passive"))
    )
    (net (code "37") (name "Net-(T1-TX-)") (class "Default")
      (node (ref "J4") (pin "2") (pinfunction "2_2") (pintype "passive"))
      (node (ref "T1") (pin "14") (pinfunction "TX-_14") (pintype "passive"))
    )
    (net (code "38") (name "Net-(U7-1V2O)") (class "Default")
      (node (ref "C42") (pin "1") (pinfunction "1_1") (pintype "passive"))
      (node (ref "U7") (pin "22") (pinfunction "1V2O_22") (pintype "output"))
    )
    (net (code "39") (name "Net-(U7-EXRES1)") (class "Default")
      (node (ref "R41") (pin "2") (pinfunction "2_2") (pintype "passive"))
      (node (ref "U7") (pin "10") (pinfunction "EXRES1_10") (pintype "bidirectional"))
    )
    (net (code "40") (name "Net-(U7-RSVD1)") (class "Default")
      (node (ref "R42") (pin "2") (pinfunction "2_2") (pintype "passive"))
      (node (ref "U7") (pin "23") (pinfunction "RSVD1_23") (pintype "input"))
    )
    (net (code "41") (name "Net-(U7-RXN)") (class "Default")
      (node (ref "R39") (pin "1") (pinfunction "1_1") (pintype "passive"))
      (node (ref "U7") (pin "5") (pinfunction "RXN_5") (pintype "input"))
    )
    (net (code "42") (name "Net-(U7-RXP)") (class "Default")
      (node (ref "R40") (pin "1") (pinfunction "1_1") (pintype "passive"))
      (node (ref "U7") (pin "6") (pinfunction "RXP_6") (pintype "input"))
    )
    (net (code "43") (name "Net-(U7-TOCAP)") (class "Default")
      (node (ref "C41") (pin "1") (pinfunction "1_1") (pintype "passive"))
      (node (ref "U7") (pin "20") (pinfunction "TOCAP_20") (pintype "output"))
    )
    (net (code "44") (name "Net-(U7-TXN)") (class "Default")
      (node (ref "R35") (pin "1") (pinfunction "1_1") (pintype "passive"))
      (node (ref "U7") (pin "1") (pinfunction "TXN_1") (pintype "output"))
    )
    (net (code "45") (name "Net-(U7-TXP)") (class "Default")
      (node (ref "R36") (pin "1") (pinfunction "1_1") (pintype "passive"))
      (node (ref "U7") (pin "2") (pinfunction "TXP_2") (pintype "output"))
    )
    (net (code "46") (name "Net-(U7-XI)") (class "Default")
      (node (ref "R33") (pin "2") (pinfunction "2_2") (pintype "passive"))
      (node (ref "U7") (pin "30") (pinfunction "XI_30") (pintype "input"))
      (node (ref "Y2") (pin "3") (pinfunction "NC_3") (pintype "passive"))
    )
    (net (code "47") (name "Net-(U7-XO)") (class "Default")
      (node (ref "R33") (pin "1") (pinfunction "1_1") (pintype "passive"))
      (node (ref "U7") (pin "31") (pinfunction "XO_31") (pintype "output"))
      (node (ref "Y2") (pin "1") (pinfunction "1_1") (pintype "passive"))
    )
    (net (code "48") (name "unconnected-(J4-Pad0)") (class "Default")
      (node (ref "J4") (pin "0") (pinfunction "0_0") (pintype "passive+no_connect"))
    )
    (net (code "49") (name "unconnected-(J4-Pad0)_1") (class "Default")
      (node (ref "J4") (pin "0") (pinfunction "0_0") (pintype "passive+no_connect"))
    )
    (net (code "50") (name "unconnected-(T1-NC-Pad4)") (class "Default")
      (node (ref "T1") (pin "4") (pinfunction "NC_4") (pintype "passive+no_connect"))
    )
    (net (code "51") (name "unconnected-(T1-NC-Pad5)") (class "Default")
      (node (ref "T1") (pin "5") (pinfunction "NC_5") (pintype "passive+no_connect"))
    )
    (net (code "52") (name "unconnected-(T1-NC-Pad12)") (class "Default")
      (node (ref "T1") (pin "12") (pinfunction "NC_12") (pintype "passive+no_connect"))
    )
    (net (code "53") (name "unconnected-(T1-NC-Pad13)") (class "Default")
      (node (ref "T1") (pin "13") (pinfunction "NC_13") (pintype "passive+no_connect"))
    )
    (net (code "54") (name "unconnected-(U7-DNC-Pad7)") (class "Default")
      (node (ref "U7") (pin "7") (pinfunction "DNC_7") (pintype "bidirectional+no_connect"))
    )
    (net (code "55") (name "unconnected-(U7-DUPLED-Pad26)") (class "Default")
      (node (ref "U7") (pin "26") (pinfunction "DUPLED_26") (pintype "output+no_connect"))
    )
    (net (code "56") (name "unconnected-(U7-RSVD2-Pad38)") (class "Default")
      (node (ref "U7") (pin "38") (pinfunction "RSVD2_38") (pintype "input+no_connect"))
    )
    (net (code "57") (name "unconnected-(U7-RSVD3-Pad39)") (class "Default")
      (node (ref "U7") (pin "39") (pinfunction "RSVD3_39") (pintype "input+no_connect"))
    )
    (net (code "58") (name "unconnected-(U7-RSVD4-Pad40)") (class "Default")
      (node (ref "U7") (pin "40") (pinfunction "RSVD4_40") (pintype "input+no_connect"))
    )
    (net (code "59") (name "unconnected-(U7-RSVD5-Pad41)") (class "Default")
      (node (ref "U7") (pin "41") (pinfunction "RSVD5_41") (pintype "input+no_connect"))
    )
    (net (code "60") (name "unconnected-(U7-RSVD6-Pad42)") (class "Default")
      (node (ref "U7") (pin "42") (pinfunction "RSVD6_42") (pintype "input+no_connect"))
    )
    (net (code "61") (name "unconnected-(U7-SPDLED-Pad24)") (class "Default")
      (node (ref "U7") (pin "24") (pinfunction "SPDLED_24") (pintype "output+no_connect"))
    )
    (net (code "62") (name "unconnected-(U7-VBG-Pad18)") (class "Default")
      (node (ref "U7") (pin "18") (pinfunction "VBG_18") (pintype "output+no_connect"))
    )
  )
)
